# untitled.net
KiCad netlist of a schematic drawn in EAGLE
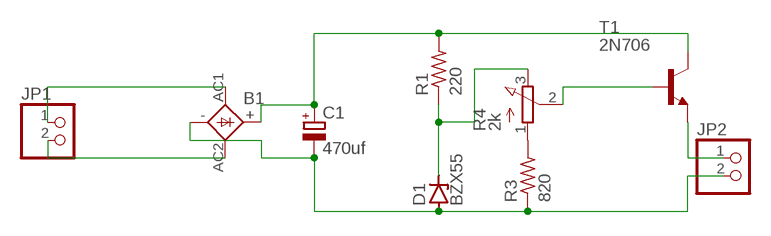
[diagram p0: schematic, sheet 1]

(export (version "E")
  (design (tool "Eeschema 10.0.6"))
  (components
    (comp (ref "B1")
      (value "1KAB")
      (footprint "eagle-import:1KAB")
      (libsource (lib "eagle-import") (part "1KAB"))
    )
    (comp (ref "C1")
      (value "470uf")
      (footprint "eagle-import:E3,5-10")
      (libsource (lib "eagle-import") (part "CPOL-EUE3.5-10"))
    )
    (comp (ref "D1")
      (value "BZX55")
      (footprint "eagle-import:DO35Z10")
      (libsource (lib "eagle-import") (part "BZX55"))
    )
    (comp (ref "JP1")
      (value "PINHD-1X2")
      (footprint "eagle-import:1X02")
      (libsource (lib "eagle-import") (part "PINHD-1X2"))
    )
    (comp (ref "JP2")
      (value "PINHD-1X2")
      (footprint "eagle-import:1X02")
      (libsource (lib "eagle-import") (part "PINHD-1X2"))
    )
    (comp (ref "R1")
      (value "220")
      (footprint "eagle-import:0309_12")
      (libsource (lib "eagle-import") (part "R-US_0309/12"))
    )
    (comp (ref "R3")
      (value "820")
      (footprint "eagle-import:0309_12")
      (libsource (lib "eagle-import") (part "R-US_0309/12"))
    )
    (comp (ref "R4")
      (value "2k")
      (footprint "eagle-import:3RP_1610N")
      (libsource (lib "eagle-import") (part "3RP/1610N"))
    )
    (comp (ref "T1")
      (value "2N706")
      (footprint "eagle-import:TO18")
      (libsource (lib "eagle-import") (part "2N706"))
    )
  )
  (nets
    (net (code "1") (name "Net-(B1-Pad-)") (class "Default")
      (node (ref "B1") (pin "-") (pinfunction "-_-") (pintype "passive"))
      (node (ref "C1") (pin "-") (pinfunction "-_-") (pintype "passive"))
      (node (ref "D1") (pin "A") (pinfunction "A_A") (pintype "passive"))
      (node (ref "JP2") (pin "2") (pinfunction "2_2") (pintype "passive"))
      (node (ref "R3") (pin "1") (pinfunction "1_1") (pintype "passive"))
    )
    (net (code "2") (name "Net-(B1-PadAC1)") (class "Default")
      (node (ref "B1") (pin "AC1") (pinfunction "AC1_AC1") (pintype "passive"))
      (node (ref "JP1") (pin "1") (pinfunction "1_1") (pintype "passive"))
    )
    (net (code "3") (name "Net-(B1-PadAC2)") (class "Default")
      (node (ref "B1") (pin "AC2") (pinfunction "AC2_AC2") (pintype "passive"))
      (node (ref "JP1") (pin "2") (pinfunction "2_2") (pintype "passive"))
    )
    (net (code "4") (name "Net-(R4-A)") (class "Default")
      (node (ref "R3") (pin "2") (pinfunction "2_2") (pintype "passive"))
      (node (ref "R4") (pin "1") (pinfunction "A_1") (pintype "passive"))
    )
    (net (code "5") (name "Net-(R4-E)") (class "Default")
      (node (ref "D1") (pin "C") (pinfunction "C_C") (pintype "passive"))
      (node (ref "R1") (pin "1") (pinfunction "1_1") (pintype "passive"))
      (node (ref "R4") (pin "3") (pinfunction "E_3") (pintype "passive"))
    )
    (net (code "6") (name "Net-(R4-S)") (class "Default")
      (node (ref "R4") (pin "2") (pinfunction "S_2") (pintype "passive"))
      (node (ref "T1") (pin "2") (pinfunction "B_2") (pintype "passive"))
    )
    (net (code "7") (name "Net-(T1-C)") (class "Default")
      (node (ref "B1") (pin "+") (pinfunction "+_+") (pintype "passive"))
      (node (ref "C1") (pin "+") (pinfunction "+_+") (pintype "passive"))
      (node (ref "R1") (pin "2") (pinfunction "2_2") (pintype "passive"))
      (node (ref "T1") (pin "3") (pinfunction "C_3") (pintype "passive"))
    )
    (net (code "8") (name "Net-(T1-E)") (class "Default")
      (node (ref "JP2") (pin "1") (pinfunction "1_1") (pintype "passive"))
      (node (ref "T1") (pin "1") (pinfunction "E_1") (pintype "passive"))
    )
  )
)
